# WS28Board.net
KiCad netlist of a schematic drawn in EAGLE
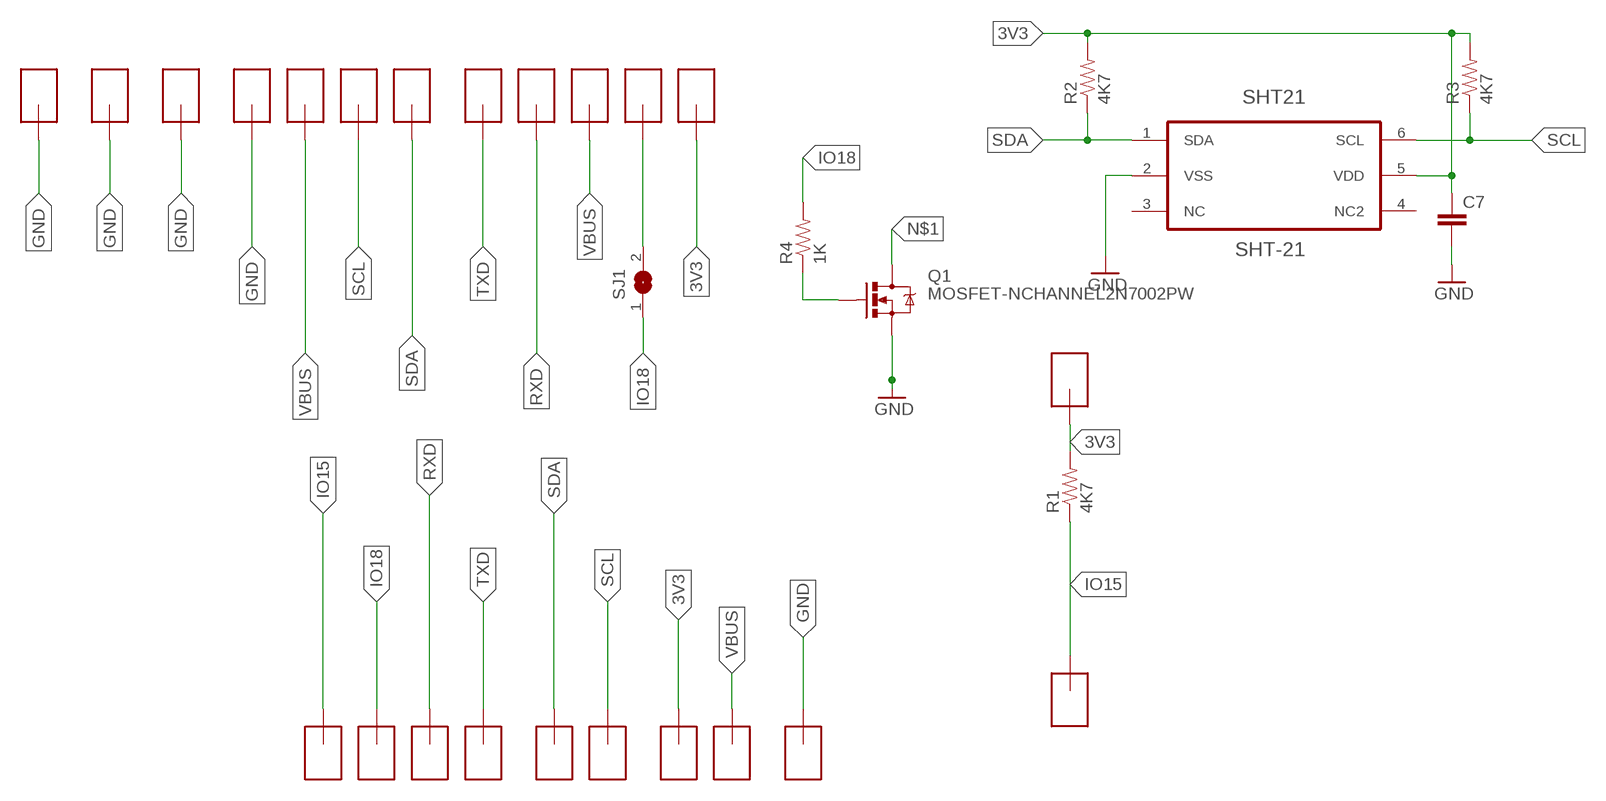
[diagram p0: schematic, sheet 1]

(export (version "E")
  (design (tool "Eeschema 10.0.6"))
  (components
    (comp (ref "C7")
      (value "CAP0603-CAP")
      (footprint "eagle-import:0603-CAP")
      (libsource (lib "eagle-import") (part "CAP0603-CAP"))
    )
    (comp (ref "GND")
      (value "SMD-PAD1")
      (footprint "eagle-import:SMD-PAD1")
      (libsource (lib "eagle-import") (part "SMD-PAD1"))
    )
    (comp (ref "GND1")
      (value "SMD-PAD1")
      (footprint "eagle-import:SMD-PAD1")
      (libsource (lib "eagle-import") (part "SMD-PAD1"))
    )
    (comp (ref "GND2")
      (value "SMD-PAD1")
      (footprint "eagle-import:SMD-PAD1")
      (libsource (lib "eagle-import") (part "SMD-PAD1"))
    )
    (comp (ref "GND3")
      (value "SMD-PAD1")
      (footprint "eagle-import:SMD-PAD1")
      (libsource (lib "eagle-import") (part "SMD-PAD1"))
    )
    (comp (ref "GND4")
      (value "SMD-PAD1")
      (footprint "eagle-import:SMD-PAD1")
      (libsource (lib "eagle-import") (part "SMD-PAD1"))
    )
    (comp (ref "Q1")
      (value "MOSFET-NCHANNEL2N7002PW")
      (footprint "eagle-import:SOT323")
      (libsource (lib "eagle-import") (part "MOSFET-NCHANNEL2N7002PW"))
    )
    (comp (ref "R1")
      (value "4K7")
      (footprint "eagle-import:0805")
      (libsource (lib "eagle-import") (part "RESISTOR0805-RES"))
    )
    (comp (ref "R2")
      (value "4K7")
      (footprint "eagle-import:0805")
      (libsource (lib "eagle-import") (part "RESISTOR0805-RES"))
    )
    (comp (ref "R3")
      (value "4K7")
      (footprint "eagle-import:0805")
      (libsource (lib "eagle-import") (part "RESISTOR0805-RES"))
    )
    (comp (ref "R4")
      (value "1K")
      (footprint "eagle-import:0805")
      (libsource (lib "eagle-import") (part "RESISTOR0805-RES"))
    )
    (comp (ref "SHT21")
      (value "SHT-21")
      (footprint "eagle-import:SHT21")
      (libsource (lib "eagle-import") (part "SHT-21"))
    )
    (comp (ref "SJ1") (value "SJ") (footprint "eagle-import:SJ") (libsource (lib "eagle-import") (part "SJ")))
    (comp (ref "U$1")
      (value "SMD-PAD1")
      (footprint "eagle-import:SMD-PAD1")
      (libsource (lib "eagle-import") (part "SMD-PAD1"))
    )
    (comp (ref "U$2")
      (value "SMD-PAD1")
      (footprint "eagle-import:SMD-PAD1")
      (libsource (lib "eagle-import") (part "SMD-PAD1"))
    )
    (comp (ref "U$3")
      (value "SMD-PAD1")
      (footprint "eagle-import:SMD-PAD1")
      (libsource (lib "eagle-import") (part "SMD-PAD1"))
    )
    (comp (ref "U$4")
      (value "SMD-PAD1")
      (footprint "eagle-import:SMD-PAD1")
      (libsource (lib "eagle-import") (part "SMD-PAD1"))
    )
    (comp (ref "U$5")
      (value "SMD-PAD1")
      (footprint "eagle-import:SMD-PAD1")
      (libsource (lib "eagle-import") (part "SMD-PAD1"))
    )
    (comp (ref "U$6")
      (value "SMD-PAD1")
      (footprint "eagle-import:SMD-PAD1")
      (libsource (lib "eagle-import") (part "SMD-PAD1"))
    )
    (comp (ref "U$7")
      (value "SMD-PAD1")
      (footprint "eagle-import:SMD-PAD1")
      (libsource (lib "eagle-import") (part "SMD-PAD1"))
    )
    (comp (ref "U$8")
      (value "SMD-PAD1")
      (footprint "eagle-import:SMD-PAD1")
      (libsource (lib "eagle-import") (part "SMD-PAD1"))
    )
    (comp (ref "U$9")
      (value "SMD-PAD1")
      (footprint "eagle-import:SMD-PAD1")
      (libsource (lib "eagle-import") (part "SMD-PAD1"))
    )
    (comp (ref "U$10")
      (value "SMD-PAD1")
      (footprint "eagle-import:SMD-PAD1")
      (libsource (lib "eagle-import") (part "SMD-PAD1"))
    )
    (comp (ref "U$11")
      (value "SMD-PAD1")
      (footprint "eagle-import:SMD-PAD1")
      (libsource (lib "eagle-import") (part "SMD-PAD1"))
    )
    (comp (ref "U$12")
      (value "SMD-PAD1")
      (footprint "eagle-import:SMD-PAD1")
      (libsource (lib "eagle-import") (part "SMD-PAD1"))
    )
    (comp (ref "U$13")
      (value "SMD-PAD1")
      (footprint "eagle-import:SMD-PAD1")
      (libsource (lib "eagle-import") (part "SMD-PAD1"))
    )
    (comp (ref "U$14")
      (value "SMD-PAD1")
      (footprint "eagle-import:SMD-PAD1")
      (libsource (lib "eagle-import") (part "SMD-PAD1"))
    )
    (comp (ref "U$15")
      (value "SMD-PAD1")
      (footprint "eagle-import:SMD-PAD1")
      (libsource (lib "eagle-import") (part "SMD-PAD1"))
    )
    (comp (ref "U$16")
      (value "SMD-PAD1")
      (footprint "eagle-import:SMD-PAD1")
      (libsource (lib "eagle-import") (part "SMD-PAD1"))
    )
    (comp (ref "U$17")
      (value "SMD-PAD1")
      (footprint "eagle-import:SMD-PAD1")
      (libsource (lib "eagle-import") (part "SMD-PAD1"))
    )
    (comp (ref "U$18")
      (value "SMD-PAD1")
      (footprint "eagle-import:SMD-PAD1")
      (libsource (lib "eagle-import") (part "SMD-PAD1"))
    )
  )
  (nets
    (net (code "1") (name "/NC") (class "Default")
      (node (ref "SHT21") (pin "3") (pinfunction "NC_3") (pintype "power_in"))
    )
    (net (code "2") (name "3V3") (class "Default")
      (node (ref "C7") (pin "1") (pinfunction "1_1") (pintype "passive"))
      (node (ref "GND4") (pin ">NAME") (pinfunction "P$1_>NAME") (pintype "bidirectional"))
      (node (ref "R1") (pin "2") (pinfunction "2_2") (pintype "passive"))
      (node (ref "R2") (pin "2") (pinfunction "2_2") (pintype "passive"))
      (node (ref "R3") (pin "2") (pinfunction "2_2") (pintype "passive"))
      (node (ref "SHT21") (pin "5") (pinfunction "VDD_5") (pintype "bidirectional"))
      (node (ref "U$13") (pin ">NAME") (pinfunction "P$1_>NAME") (pintype "bidirectional"))
      (node (ref "U$14") (pin ">NAME") (pinfunction "P$1_>NAME") (pintype "bidirectional"))
    )
    (net (code "3") (name "GND") (class "Default")
      (node (ref "C7") (pin "2") (pinfunction "2_2") (pintype "passive"))
      (node (ref "Q1") (pin "2") (pinfunction "S_2") (pintype "passive"))
      (node (ref "SHT21") (pin "2") (pinfunction "VSS_2") (pintype "input"))
      (node (ref "U$1") (pin ">NAME") (pinfunction "P$1_>NAME") (pintype "bidirectional"))
      (node (ref "U$10") (pin ">NAME") (pinfunction "P$1_>NAME") (pintype "bidirectional"))
      (node (ref "U$15") (pin ">NAME") (pinfunction "P$1_>NAME") (pintype "bidirectional"))
      (node (ref "U$16") (pin ">NAME") (pinfunction "P$1_>NAME") (pintype "bidirectional"))
      (node (ref "U$17") (pin ">NAME") (pinfunction "P$1_>NAME") (pintype "bidirectional"))
    )
    (net (code "4") (name "IO15") (class "Default")
      (node (ref "GND2") (pin ">NAME") (pinfunction "P$1_>NAME") (pintype "bidirectional"))
      (node (ref "R1") (pin "1") (pinfunction "1_1") (pintype "passive"))
      (node (ref "U$18") (pin ">NAME") (pinfunction "P$1_>NAME") (pintype "bidirectional"))
    )
    (net (code "5") (name "IO18") (class "Default")
      (node (ref "R4") (pin "2") (pinfunction "2_2") (pintype "passive"))
      (node (ref "SJ1") (pin "1") (pinfunction "1_1") (pintype "passive"))
      (node (ref "U$9") (pin ">NAME") (pinfunction "P$1_>NAME") (pintype "bidirectional"))
    )
    (net (code "6") (name "N$1") (class "Default")
      (node (ref "GND") (pin ">NAME") (pinfunction "P$1_>NAME") (pintype "bidirectional"))
      (node (ref "Q1") (pin "3") (pinfunction "D_3") (pintype "passive"))
      (node (ref "SJ1") (pin "2") (pinfunction "2_2") (pintype "passive"))
    )
    (net (code "7") (name "Net-(Q1-G)") (class "Default")
      (node (ref "Q1") (pin "1") (pinfunction "G_1") (pintype "passive"))
      (node (ref "R4") (pin "1") (pinfunction "1_1") (pintype "passive"))
    )
    (net (code "8") (name "RXD") (class "Default")
      (node (ref "U$3") (pin ">NAME") (pinfunction "P$1_>NAME") (pintype "bidirectional"))
      (node (ref "U$8") (pin ">NAME") (pinfunction "P$1_>NAME") (pintype "bidirectional"))
    )
    (net (code "9") (name "SCL") (class "Default")
      (node (ref "R3") (pin "1") (pinfunction "1_1") (pintype "passive"))
      (node (ref "SHT21") (pin "6") (pinfunction "SCL_6") (pintype "bidirectional"))
      (node (ref "U$12") (pin ">NAME") (pinfunction "P$1_>NAME") (pintype "bidirectional"))
      (node (ref "U$6") (pin ">NAME") (pinfunction "P$1_>NAME") (pintype "bidirectional"))
    )
    (net (code "10") (name "SDA") (class "Default")
      (node (ref "GND1") (pin ">NAME") (pinfunction "P$1_>NAME") (pintype "bidirectional"))
      (node (ref "GND3") (pin ">NAME") (pinfunction "P$1_>NAME") (pintype "bidirectional"))
      (node (ref "R2") (pin "1") (pinfunction "1_1") (pintype "passive"))
      (node (ref "SHT21") (pin "1") (pinfunction "SDA_1") (pintype "power_in"))
    )
    (net (code "11") (name "TXD") (class "Default")
      (node (ref "U$2") (pin ">NAME") (pinfunction "P$1_>NAME") (pintype "bidirectional"))
      (node (ref "U$7") (pin ">NAME") (pinfunction "P$1_>NAME") (pintype "bidirectional"))
    )
    (net (code "12") (name "VBUS") (class "Default")
      (node (ref "U$11") (pin ">NAME") (pinfunction "P$1_>NAME") (pintype "bidirectional"))
      (node (ref "U$4") (pin ">NAME") (pinfunction "P$1_>NAME") (pintype "bidirectional"))
      (node (ref "U$5") (pin ">NAME") (pinfunction "P$1_>NAME") (pintype "bidirectional"))
    )
    (net (code "13") (name "unconnected-(SHT21-NC2-Pad4)") (class "Default")
      (node (ref "SHT21") (pin "4") (pinfunction "NC2_4") (pintype "bidirectional"))
    )
  )
)
